# neato_lcd_adapter.net
KiCad netlist of a schematic drawn in EAGLE
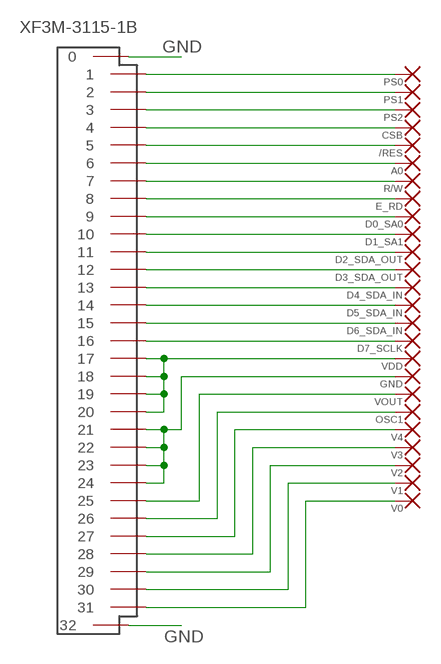
[diagram p0: schematic, sheet 1]

(export (version "E")
  (design (tool "Eeschema 10.0.6"))
  (components
    (comp (ref "/RES")
      (value "SMD2")
      (footprint "eagle-import:SMD_PAD")
      (libsource (lib "eagle-import") (part "SMD2"))
    )
    (comp (ref "A0")
      (value "SMD2")
      (footprint "eagle-import:SMD_PAD")
      (libsource (lib "eagle-import") (part "SMD2"))
    )
    (comp (ref "CSB")
      (value "SMD2")
      (footprint "eagle-import:SMD_PAD")
      (libsource (lib "eagle-import") (part "SMD2"))
    )
    (comp (ref "D0_SA0")
      (value "SMD2")
      (footprint "eagle-import:SMD_PAD")
      (libsource (lib "eagle-import") (part "SMD2"))
    )
    (comp (ref "D1_SA1")
      (value "SMD2")
      (footprint "eagle-import:SMD_PAD")
      (libsource (lib "eagle-import") (part "SMD2"))
    )
    (comp (ref "D2_SDA_OUT")
      (value "SMD2")
      (footprint "eagle-import:SMD_PAD")
      (libsource (lib "eagle-import") (part "SMD2"))
    )
    (comp (ref "D3_SDA_OUT")
      (value "SMD2")
      (footprint "eagle-import:SMD_PAD")
      (libsource (lib "eagle-import") (part "SMD2"))
    )
    (comp (ref "D4_SDA_IN")
      (value "SMD2")
      (footprint "eagle-import:SMD_PAD")
      (libsource (lib "eagle-import") (part "SMD2"))
    )
    (comp (ref "D5_SDA_IN")
      (value "SMD2")
      (footprint "eagle-import:SMD_PAD")
      (libsource (lib "eagle-import") (part "SMD2"))
    )
    (comp (ref "D6_SDA_IN")
      (value "SMD2")
      (footprint "eagle-import:SMD_PAD")
      (libsource (lib "eagle-import") (part "SMD2"))
    )
    (comp (ref "D7_SCLK")
      (value "SMD2")
      (footprint "eagle-import:SMD_PAD")
      (libsource (lib "eagle-import") (part "SMD2"))
    )
    (comp (ref "E_RD")
      (value "SMD2")
      (footprint "eagle-import:SMD_PAD")
      (libsource (lib "eagle-import") (part "SMD2"))
    )
    (comp (ref "GND")
      (value "SMD2")
      (footprint "eagle-import:SMD_PAD")
      (libsource (lib "eagle-import") (part "SMD2"))
    )
    (comp (ref "LCD")
      (value "XF3M-3115-1B")
      (footprint "eagle-import:FPC-31P-0.5MM")
      (libsource (lib "eagle-import") (part "XF3M-3115-1B"))
    )
    (comp (ref "OSC1")
      (value "SMD2")
      (footprint "eagle-import:SMD_PAD")
      (libsource (lib "eagle-import") (part "SMD2"))
    )
    (comp (ref "PS0")
      (value "SMD2")
      (footprint "eagle-import:SMD_PAD")
      (libsource (lib "eagle-import") (part "SMD2"))
    )
    (comp (ref "PS1")
      (value "SMD2")
      (footprint "eagle-import:SMD_PAD")
      (libsource (lib "eagle-import") (part "SMD2"))
    )
    (comp (ref "PS2")
      (value "SMD2")
      (footprint "eagle-import:SMD_PAD")
      (libsource (lib "eagle-import") (part "SMD2"))
    )
    (comp (ref "R/W")
      (value "SMD2")
      (footprint "eagle-import:SMD_PAD")
      (libsource (lib "eagle-import") (part "SMD2"))
    )
    (comp (ref "V0")
      (value "SMD2")
      (footprint "eagle-import:SMD_PAD")
      (libsource (lib "eagle-import") (part "SMD2"))
    )
    (comp (ref "V1")
      (value "SMD2")
      (footprint "eagle-import:SMD_PAD")
      (libsource (lib "eagle-import") (part "SMD2"))
    )
    (comp (ref "V2")
      (value "SMD2")
      (footprint "eagle-import:SMD_PAD")
      (libsource (lib "eagle-import") (part "SMD2"))
    )
    (comp (ref "V3")
      (value "SMD2")
      (footprint "eagle-import:SMD_PAD")
      (libsource (lib "eagle-import") (part "SMD2"))
    )
    (comp (ref "V4")
      (value "SMD2")
      (footprint "eagle-import:SMD_PAD")
      (libsource (lib "eagle-import") (part "SMD2"))
    )
    (comp (ref "VDD")
      (value "SMD2")
      (footprint "eagle-import:SMD_PAD")
      (libsource (lib "eagle-import") (part "SMD2"))
    )
    (comp (ref "VOUT")
      (value "SMD2")
      (footprint "eagle-import:SMD_PAD")
      (libsource (lib "eagle-import") (part "SMD2"))
    )
  )
  (nets
    (net (code "1") (name "/GND") (class "Default")
      (node (ref "LCD") (pin "P$1") (pinfunction "0_P$1") (pintype "bidirectional"))
      (node (ref "LCD") (pin "P$2") (pinfunction "32_P$2") (pintype "bidirectional"))
    )
    (net (code "2") (name "Net-(/RES-P)") (class "Default")
      (node (ref "/RES") (pin "1") (pinfunction "P_1") (pintype "passive"))
      (node (ref "LCD") (pin "P$7") (pinfunction "5_P$7") (pintype "bidirectional"))
    )
    (net (code "3") (name "Net-(A0-P)") (class "Default")
      (node (ref "A0") (pin "1") (pinfunction "P_1") (pintype "passive"))
      (node (ref "LCD") (pin "P$8") (pinfunction "6_P$8") (pintype "bidirectional"))
    )
    (net (code "4") (name "Net-(CSB-P)") (class "Default")
      (node (ref "CSB") (pin "1") (pinfunction "P_1") (pintype "passive"))
      (node (ref "LCD") (pin "P$6") (pinfunction "4_P$6") (pintype "bidirectional"))
    )
    (net (code "5") (name "Net-(D0_SA0-P)") (class "Default")
      (node (ref "D0_SA0") (pin "1") (pinfunction "P_1") (pintype "passive"))
      (node (ref "LCD") (pin "P$11") (pinfunction "9_P$11") (pintype "bidirectional"))
    )
    (net (code "6") (name "Net-(D1_SA1-P)") (class "Default")
      (node (ref "D1_SA1") (pin "1") (pinfunction "P_1") (pintype "passive"))
      (node (ref "LCD") (pin "P$12") (pinfunction "10_P$12") (pintype "bidirectional"))
    )
    (net (code "7") (name "Net-(D2_SDA_OUT-P)") (class "Default")
      (node (ref "D2_SDA_OUT") (pin "1") (pinfunction "P_1") (pintype "passive"))
      (node (ref "LCD") (pin "P$13") (pinfunction "11_P$13") (pintype "bidirectional"))
    )
    (net (code "8") (name "Net-(D3_SDA_OUT-P)") (class "Default")
      (node (ref "D3_SDA_OUT") (pin "1") (pinfunction "P_1") (pintype "passive"))
      (node (ref "LCD") (pin "P$14") (pinfunction "12_P$14") (pintype "bidirectional"))
    )
    (net (code "9") (name "Net-(D4_SDA_IN-P)") (class "Default")
      (node (ref "D4_SDA_IN") (pin "1") (pinfunction "P_1") (pintype "passive"))
      (node (ref "LCD") (pin "P$15") (pinfunction "13_P$15") (pintype "bidirectional"))
    )
    (net (code "10") (name "Net-(D5_SDA_IN-P)") (class "Default")
      (node (ref "D5_SDA_IN") (pin "1") (pinfunction "P_1") (pintype "passive"))
      (node (ref "LCD") (pin "P$16") (pinfunction "14_P$16") (pintype "bidirectional"))
    )
    (net (code "11") (name "Net-(D6_SDA_IN-P)") (class "Default")
      (node (ref "D6_SDA_IN") (pin "1") (pinfunction "P_1") (pintype "passive"))
      (node (ref "LCD") (pin "P$17") (pinfunction "15_P$17") (pintype "bidirectional"))
    )
    (net (code "12") (name "Net-(D7_SCLK-P)") (class "Default")
      (node (ref "D7_SCLK") (pin "1") (pinfunction "P_1") (pintype "passive"))
      (node (ref "LCD") (pin "P$18") (pinfunction "16_P$18") (pintype "bidirectional"))
    )
    (net (code "13") (name "Net-(E_RD-P)") (class "Default")
      (node (ref "E_RD") (pin "1") (pinfunction "P_1") (pintype "passive"))
      (node (ref "LCD") (pin "P$10") (pinfunction "8_P$10") (pintype "bidirectional"))
    )
    (net (code "14") (name "Net-(GND-P)") (class "Default")
      (node (ref "GND") (pin "1") (pinfunction "P_1") (pintype "passive"))
      (node (ref "LCD") (pin "P$23") (pinfunction "21_P$23") (pintype "bidirectional"))
      (node (ref "LCD") (pin "P$24") (pinfunction "22_P$24") (pintype "bidirectional"))
      (node (ref "LCD") (pin "P$25") (pinfunction "23_P$25") (pintype "bidirectional"))
      (node (ref "LCD") (pin "P$26") (pinfunction "24_P$26") (pintype "bidirectional"))
    )
    (net (code "15") (name "Net-(LCD-1)") (class "Default")
      (node (ref "LCD") (pin "P$3") (pinfunction "1_P$3") (pintype "bidirectional"))
      (node (ref "PS0") (pin "1") (pinfunction "P_1") (pintype "passive"))
    )
    (net (code "16") (name "Net-(LCD-2)") (class "Default")
      (node (ref "LCD") (pin "P$4") (pinfunction "2_P$4") (pintype "bidirectional"))
      (node (ref "PS1") (pin "1") (pinfunction "P_1") (pintype "passive"))
    )
    (net (code "17") (name "Net-(LCD-3)") (class "Default")
      (node (ref "LCD") (pin "P$5") (pinfunction "3_P$5") (pintype "bidirectional"))
      (node (ref "PS2") (pin "1") (pinfunction "P_1") (pintype "passive"))
    )
    (net (code "18") (name "Net-(LCD-7)") (class "Default")
      (node (ref "LCD") (pin "P$9") (pinfunction "7_P$9") (pintype "bidirectional"))
      (node (ref "R/W") (pin "1") (pinfunction "P_1") (pintype "passive"))
    )
    (net (code "19") (name "Net-(LCD-17)") (class "Default")
      (node (ref "LCD") (pin "P$19") (pinfunction "17_P$19") (pintype "bidirectional"))
      (node (ref "LCD") (pin "P$20") (pinfunction "18_P$20") (pintype "bidirectional"))
      (node (ref "LCD") (pin "P$21") (pinfunction "19_P$21") (pintype "bidirectional"))
      (node (ref "LCD") (pin "P$22") (pinfunction "20_P$22") (pintype "bidirectional"))
      (node (ref "VDD") (pin "1") (pinfunction "P_1") (pintype "passive"))
    )
    (net (code "20") (name "Net-(LCD-25)") (class "Default")
      (node (ref "LCD") (pin "P$27") (pinfunction "25_P$27") (pintype "bidirectional"))
      (node (ref "VOUT") (pin "1") (pinfunction "P_1") (pintype "passive"))
    )
    (net (code "21") (name "Net-(LCD-26)") (class "Default")
      (node (ref "LCD") (pin "P$28") (pinfunction "26_P$28") (pintype "bidirectional"))
      (node (ref "OSC1") (pin "1") (pinfunction "P_1") (pintype "passive"))
    )
    (net (code "22") (name "Net-(LCD-27)") (class "Default")
      (node (ref "LCD") (pin "P$29") (pinfunction "27_P$29") (pintype "bidirectional"))
      (node (ref "V4") (pin "1") (pinfunction "P_1") (pintype "passive"))
    )
    (net (code "23") (name "Net-(LCD-28)") (class "Default")
      (node (ref "LCD") (pin "P$30") (pinfunction "28_P$30") (pintype "bidirectional"))
      (node (ref "V3") (pin "1") (pinfunction "P_1") (pintype "passive"))
    )
    (net (code "24") (name "Net-(LCD-29)") (class "Default")
      (node (ref "LCD") (pin "P$31") (pinfunction "29_P$31") (pintype "bidirectional"))
      (node (ref "V2") (pin "1") (pinfunction "P_1") (pintype "passive"))
    )
    (net (code "25") (name "Net-(LCD-30)") (class "Default")
      (node (ref "LCD") (pin "P$32") (pinfunction "30_P$32") (pintype "bidirectional"))
      (node (ref "V1") (pin "1") (pinfunction "P_1") (pintype "passive"))
    )
    (net (code "26") (name "Net-(LCD-31)") (class "Default")
      (node (ref "LCD") (pin "P$33") (pinfunction "31_P$33") (pintype "bidirectional"))
      (node (ref "V0") (pin "1") (pinfunction "P_1") (pintype "passive"))
    )
  )
)
